# atmega8_dip.net
KiCad netlist of a schematic drawn in EAGLE
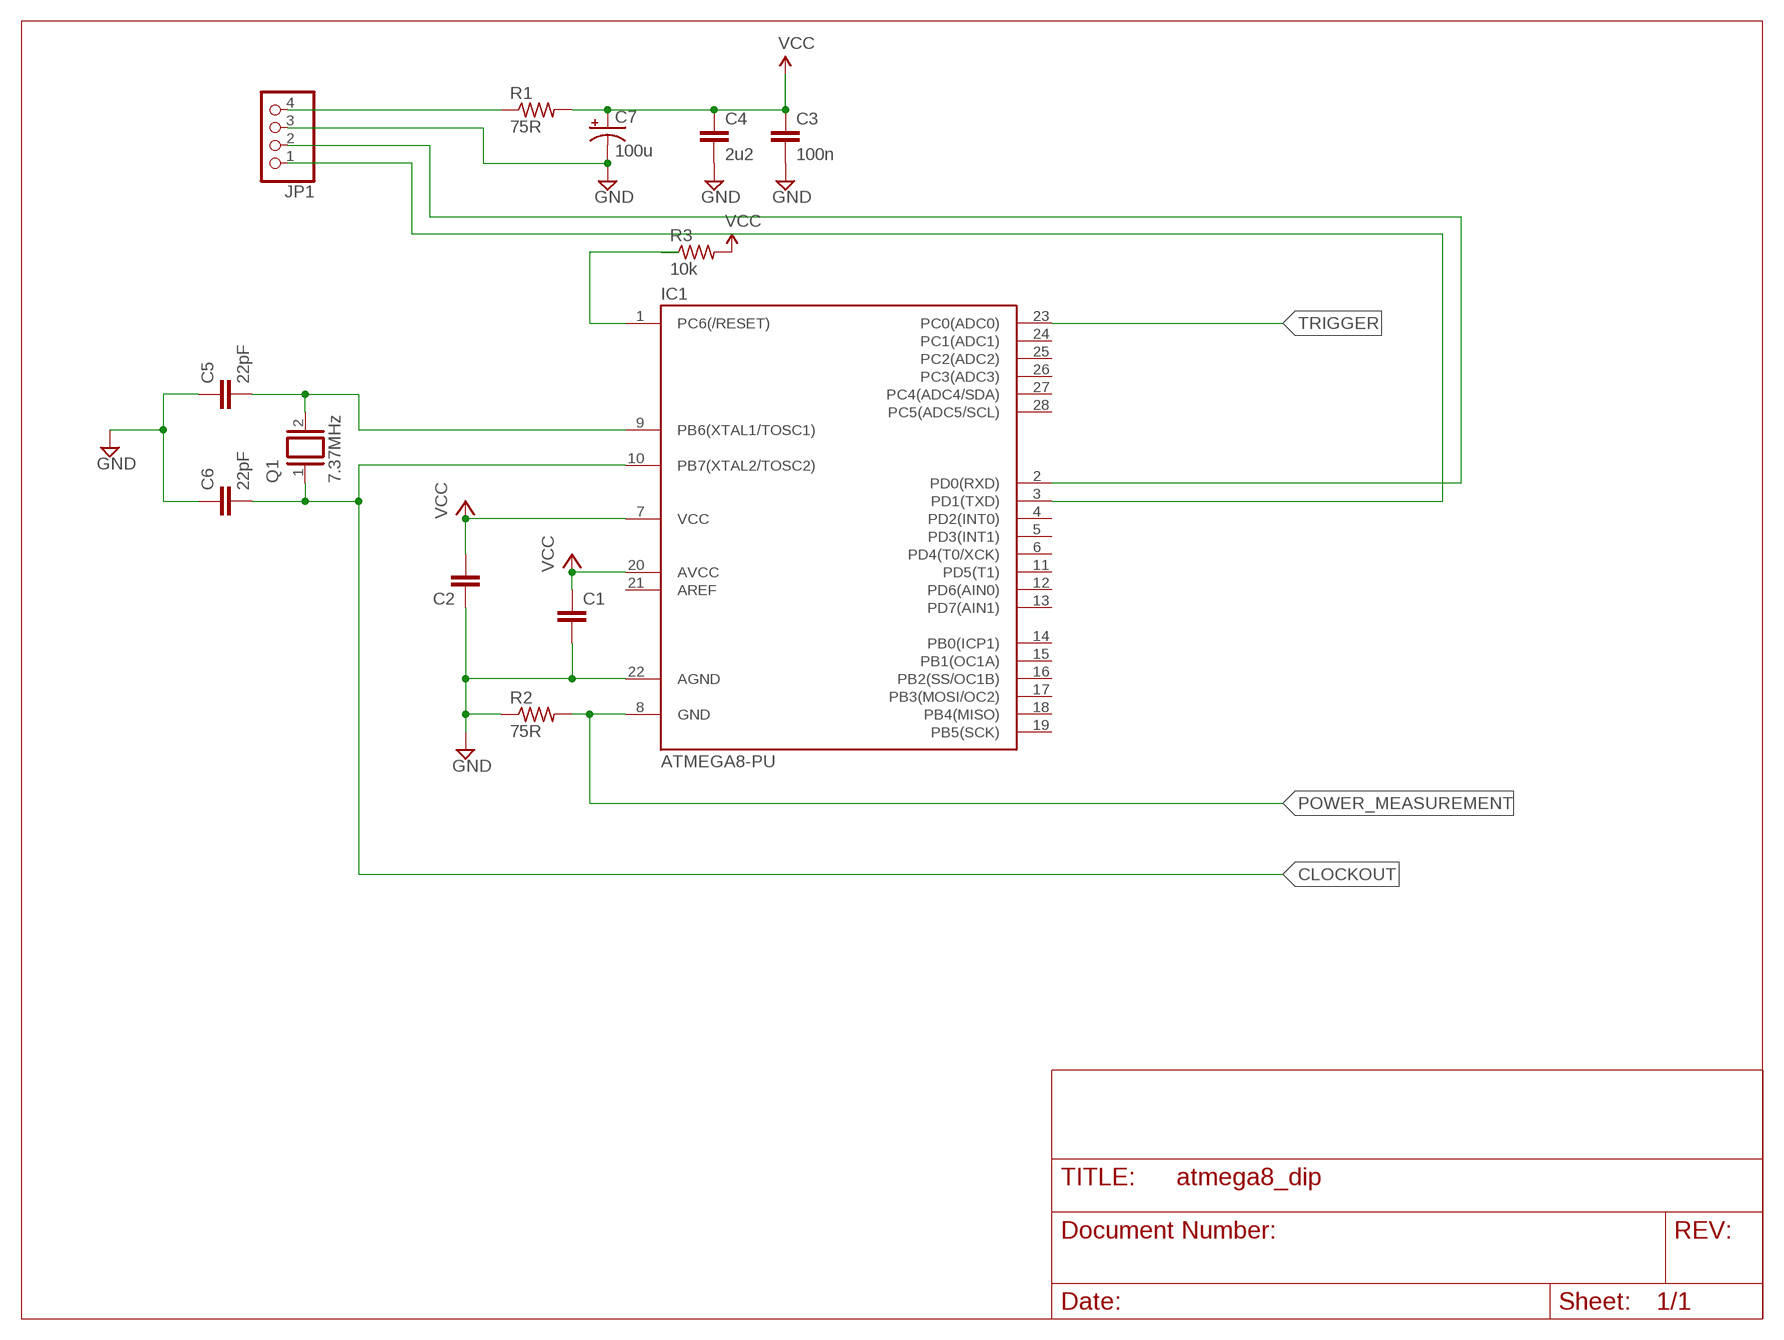
[diagram p0: schematic, sheet 1]

(export (version "E")
  (design (tool "Eeschema 10.0.6"))
  (components
    (comp (ref "C1")
      (value "C-EUC0805")
      (footprint "eagle-import:C0805")
      (libsource (lib "eagle-import") (part "C-EUC0805"))
    )
    (comp (ref "C2")
      (value "C-EUC0805")
      (footprint "eagle-import:C0805")
      (libsource (lib "eagle-import") (part "C-EUC0805"))
    )
    (comp (ref "C3")
      (value "100n")
      (footprint "eagle-import:C0805")
      (libsource (lib "eagle-import") (part "C-EUC0805"))
    )
    (comp (ref "C4")
      (value "2u2")
      (footprint "eagle-import:C0805")
      (libsource (lib "eagle-import") (part "C-EUC0805"))
    )
    (comp (ref "C5")
      (value "22pF")
      (footprint "eagle-import:C0805")
      (libsource (lib "eagle-import") (part "C-EUC0805"))
    )
    (comp (ref "C6")
      (value "22pF")
      (footprint "eagle-import:C0805")
      (libsource (lib "eagle-import") (part "C-EUC0805"))
    )
    (comp (ref "C7")
      (value "100u")
      (footprint "eagle-import:140CLH-0810")
      (libsource (lib "eagle-import") (part "CPOL-US140CLH-0810"))
    )
    (comp (ref "IC1")
      (value "ATMEGA8-PU")
      (footprint "eagle-import:DIL28-3")
      (libsource (lib "eagle-import") (part "ATMEGA8-PU"))
    )
    (comp (ref "JP1")
      (value "PINHD-1X4/90")
      (footprint "eagle-import:1X04_90")
      (libsource (lib "eagle-import") (part "PINHD-1X4/90"))
    )
    (comp (ref "Q1")
      (value "7.37MHz")
      (footprint "eagle-import:Q")
      (libsource (lib "eagle-import") (part "XTAL"))
    )
    (comp (ref "R1")
      (value "75R")
      (footprint "eagle-import:M0805")
      (libsource (lib "eagle-import") (part "R-US_M0805"))
    )
    (comp (ref "R2")
      (value "75R")
      (footprint "eagle-import:R0805")
      (libsource (lib "eagle-import") (part "resistor_R-US_R0805"))
    )
    (comp (ref "R3")
      (value "10k")
      (footprint "eagle-import:M0805")
      (libsource (lib "eagle-import") (part "R-US_M0805"))
    )
  )
  (nets
    (net (code "1") (name "CLOCKOUT") (class "Default")
      (node (ref "C6") (pin "2") (pinfunction "2_2") (pintype "passive"))
      (node (ref "IC1") (pin "10") (pinfunction "PB7(XTAL2/TOSC2)_10") (pintype "bidirectional"))
      (node (ref "Q1") (pin "1") (pinfunction "1_1") (pintype "passive"))
    )
    (net (code "2") (name "GND") (class "Default")
      (node (ref "C1") (pin "2") (pinfunction "2_2") (pintype "passive"))
      (node (ref "C2") (pin "1") (pinfunction "1_1") (pintype "passive"))
      (node (ref "C3") (pin "2") (pinfunction "2_2") (pintype "passive"))
      (node (ref "C4") (pin "2") (pinfunction "2_2") (pintype "passive"))
      (node (ref "C5") (pin "1") (pinfunction "1_1") (pintype "passive"))
      (node (ref "C6") (pin "1") (pinfunction "1_1") (pintype "passive"))
      (node (ref "C7") (pin "-") (pinfunction "-_-") (pintype "passive"))
      (node (ref "IC1") (pin "22") (pinfunction "AGND_22") (pintype "power_in"))
      (node (ref "JP1") (pin "3") (pinfunction "3_3") (pintype "passive"))
      (node (ref "R2") (pin "1") (pinfunction "1_1") (pintype "passive"))
    )
    (net (code "3") (name "Net-(IC1-PB6(XTAL1{slash}TOSC1))") (class "Default")
      (node (ref "C5") (pin "2") (pinfunction "2_2") (pintype "passive"))
      (node (ref "IC1") (pin "9") (pinfunction "PB6(XTAL1/TOSC1)_9") (pintype "bidirectional"))
      (node (ref "Q1") (pin "2") (pinfunction "2_2") (pintype "passive"))
    )
    (net (code "4") (name "Net-(IC1-PD0(RXD))") (class "Default")
      (node (ref "IC1") (pin "2") (pinfunction "PD0(RXD)_2") (pintype "bidirectional"))
      (node (ref "JP1") (pin "2") (pinfunction "2_2") (pintype "passive"))
    )
    (net (code "5") (name "Net-(IC1-PD1(TXD))") (class "Default")
      (node (ref "IC1") (pin "3") (pinfunction "PD1(TXD)_3") (pintype "bidirectional"))
      (node (ref "JP1") (pin "1") (pinfunction "1_1") (pintype "passive"))
    )
    (net (code "6") (name "Net-(JP1-Pad4)") (class "Default")
      (node (ref "JP1") (pin "4") (pinfunction "4_4") (pintype "passive"))
      (node (ref "R1") (pin "1") (pinfunction "1_1") (pintype "passive"))
    )
    (net (code "7") (name "POWER_MEASUREMENT") (class "Default")
      (node (ref "IC1") (pin "8") (pinfunction "GND_8") (pintype "power_in"))
      (node (ref "R2") (pin "2") (pinfunction "2_2") (pintype "passive"))
    )
    (net (code "8") (name "TRIGGER") (class "Default")
      (node (ref "IC1") (pin "23") (pinfunction "PC0(ADC0)_23") (pintype "bidirectional"))
    )
    (net (code "9") (name "VCC") (class "Default")
      (node (ref "C1") (pin "1") (pinfunction "1_1") (pintype "passive"))
      (node (ref "C2") (pin "2") (pinfunction "2_2") (pintype "passive"))
      (node (ref "C3") (pin "1") (pinfunction "1_1") (pintype "passive"))
      (node (ref "C4") (pin "1") (pinfunction "1_1") (pintype "passive"))
      (node (ref "C7") (pin "+") (pinfunction "+_+") (pintype "passive"))
      (node (ref "IC1") (pin "20") (pinfunction "AVCC_20") (pintype "passive"))
      (node (ref "IC1") (pin "7") (pinfunction "VCC_7") (pintype "power_in"))
      (node (ref "R1") (pin "2") (pinfunction "2_2") (pintype "passive"))
      (node (ref "R3") (pin "2") (pinfunction "2_2") (pintype "passive"))
    )
    (net (code "10") (name "unconnected-(IC1-AREF-Pad21)") (class "Default")
      (node (ref "IC1") (pin "21") (pinfunction "AREF_21") (pintype "passive"))
    )
    (net (code "11") (name "unconnected-(IC1-PB0(ICP1)-Pad14)") (class "Default")
      (node (ref "IC1") (pin "14") (pinfunction "PB0(ICP1)_14") (pintype "bidirectional"))
    )
    (net (code "12") (name "unconnected-(IC1-PB1(OC1A)-Pad15)") (class "Default")
      (node (ref "IC1") (pin "15") (pinfunction "PB1(OC1A)_15") (pintype "bidirectional"))
    )
    (net (code "13") (name "unconnected-(IC1-PB2(SS{slash}OC1B)-Pad16)") (class "Default")
      (node (ref "IC1") (pin "16") (pinfunction "PB2(SS/OC1B)_16") (pintype "bidirectional"))
    )
    (net (code "14") (name "unconnected-(IC1-PB3(MOSI{slash}OC2)-Pad17)") (class "Default")
      (node (ref "IC1") (pin "17") (pinfunction "PB3(MOSI/OC2)_17") (pintype "bidirectional"))
    )
    (net (code "15") (name "unconnected-(IC1-PB4(MISO)-Pad18)") (class "Default")
      (node (ref "IC1") (pin "18") (pinfunction "PB4(MISO)_18") (pintype "bidirectional"))
    )
    (net (code "16") (name "unconnected-(IC1-PB5(SCK)-Pad19)") (class "Default")
      (node (ref "IC1") (pin "19") (pinfunction "PB5(SCK)_19") (pintype "bidirectional"))
    )
    (net (code "17") (name "unconnected-(IC1-PC1(ADC1)-Pad24)") (class "Default")
      (node (ref "IC1") (pin "24") (pinfunction "PC1(ADC1)_24") (pintype "bidirectional"))
    )
    (net (code "18") (name "unconnected-(IC1-PC2(ADC2)-Pad25)") (class "Default")
      (node (ref "IC1") (pin "25") (pinfunction "PC2(ADC2)_25") (pintype "bidirectional"))
    )
    (net (code "19") (name "unconnected-(IC1-PC3(ADC3)-Pad26)") (class "Default")
      (node (ref "IC1") (pin "26") (pinfunction "PC3(ADC3)_26") (pintype "bidirectional"))
    )
    (net (code "20") (name "unconnected-(IC1-PC4(ADC4{slash}SDA)-Pad27)") (class "Default")
      (node (ref "IC1") (pin "27") (pinfunction "PC4(ADC4/SDA)_27") (pintype "bidirectional"))
    )
    (net (code "21") (name "unconnected-(IC1-PC5(ADC5{slash}SCL)-Pad28)") (class "Default")
      (node (ref "IC1") (pin "28") (pinfunction "PC5(ADC5/SCL)_28") (pintype "bidirectional"))
    )
    (net (code "22") (name "unconnected-(IC1-PC6({slash}RESET)-Pad1)") (class "Default")
      (node (ref "IC1") (pin "1") (pinfunction "PC6(/RESET)_1") (pintype "bidirectional"))
    )
    (net (code "23") (name "unconnected-(IC1-PD2(INT0)-Pad4)") (class "Default")
      (node (ref "IC1") (pin "4") (pinfunction "PD2(INT0)_4") (pintype "bidirectional"))
    )
    (net (code "24") (name "unconnected-(IC1-PD3(INT1)-Pad5)") (class "Default")
      (node (ref "IC1") (pin "5") (pinfunction "PD3(INT1)_5") (pintype "bidirectional"))
    )
    (net (code "25") (name "unconnected-(IC1-PD4(T0{slash}XCK)-Pad6)") (class "Default")
      (node (ref "IC1") (pin "6") (pinfunction "PD4(T0/XCK)_6") (pintype "bidirectional"))
    )
    (net (code "26") (name "unconnected-(IC1-PD5(T1)-Pad11)") (class "Default")
      (node (ref "IC1") (pin "11") (pinfunction "PD5(T1)_11") (pintype "bidirectional"))
    )
    (net (code "27") (name "unconnected-(IC1-PD6(AIN0)-Pad12)") (class "Default")
      (node (ref "IC1") (pin "12") (pinfunction "PD6(AIN0)_12") (pintype "bidirectional"))
    )
    (net (code "28") (name "unconnected-(IC1-PD7(AIN1)-Pad13)") (class "Default")
      (node (ref "IC1") (pin "13") (pinfunction "PD7(AIN1)_13") (pintype "bidirectional"))
    )
    (net (code "29") (name "unconnected-(R3-Pad1)") (class "Default")
      (node (ref "R3") (pin "1") (pinfunction "1_1") (pintype "passive"))
    )
  )
)
